# 001_full_version.net
KiCad netlist of a schematic drawn in EAGLE
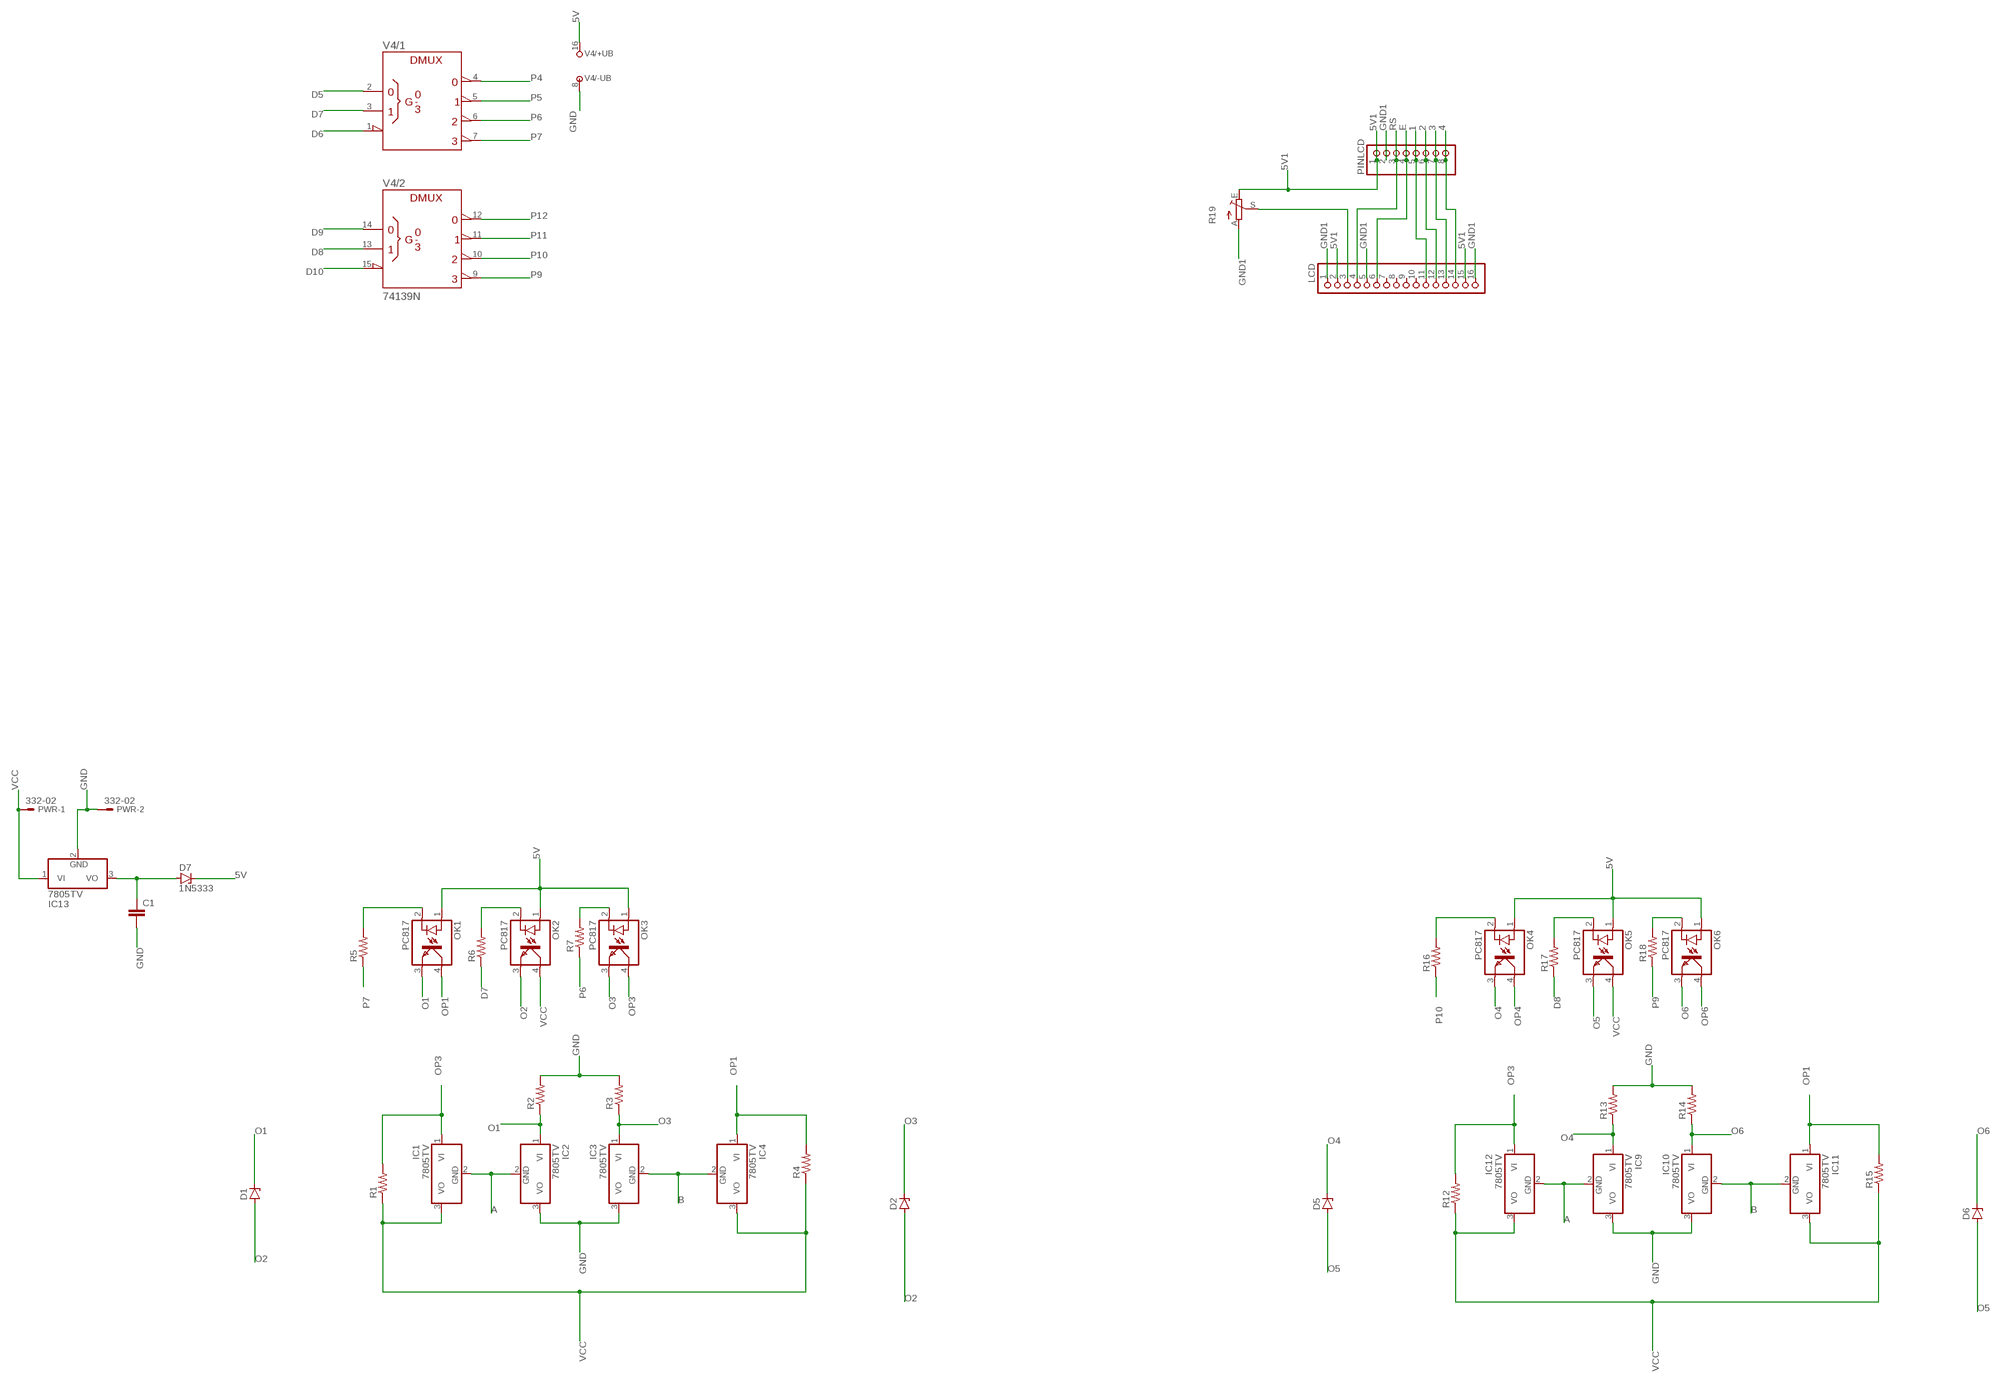
[diagram p0: schematic, sheet 1]

(export (version "E")
  (design (tool "Eeschema 10.0.6"))
  (components
    (comp (ref "C1")
      (value "C2,5-3")
      (footprint "eagle-import:C2.5-3")
      (libsource (lib "eagle-import") (part "C2,5-3"))
    )
    (comp (ref "D1")
      (value "ZENER-DIODEDO41Z10")
      (footprint "eagle-import:DO41Z10")
      (libsource (lib "eagle-import") (part "ZENER-DIODEDO41Z10"))
    )
    (comp (ref "D2")
      (value "ZENER-DIODEDO41Z10")
      (footprint "eagle-import:DO41Z10")
      (libsource (lib "eagle-import") (part "ZENER-DIODEDO41Z10"))
    )
    (comp (ref "D5")
      (value "ZENER-DIODEDO41Z10")
      (footprint "eagle-import:DO41Z10")
      (libsource (lib "eagle-import") (part "ZENER-DIODEDO41Z10"))
    )
    (comp (ref "D6")
      (value "ZENER-DIODEDO41Z10")
      (footprint "eagle-import:DO41Z10")
      (libsource (lib "eagle-import") (part "ZENER-DIODEDO41Z10"))
    )
    (comp (ref "D7")
      (value "1N5333")
      (footprint "eagle-import:C1702-15")
      (libsource (lib "eagle-import") (part "1N5333"))
    )
    (comp (ref "IC1")
      (value "7805TV")
      (footprint "eagle-import:TO220V")
      (libsource (lib "eagle-import") (part "78TV05"))
    )
    (comp (ref "IC2")
      (value "7805TV")
      (footprint "eagle-import:TO220V")
      (libsource (lib "eagle-import") (part "78TV05"))
    )
    (comp (ref "IC3")
      (value "7805TV")
      (footprint "eagle-import:TO220V")
      (libsource (lib "eagle-import") (part "78TV05"))
    )
    (comp (ref "IC4")
      (value "7805TV")
      (footprint "eagle-import:TO220V")
      (libsource (lib "eagle-import") (part "78TV05"))
    )
    (comp (ref "IC9")
      (value "7805TV")
      (footprint "eagle-import:TO220V")
      (libsource (lib "eagle-import") (part "78TV05"))
    )
    (comp (ref "IC10")
      (value "7805TV")
      (footprint "eagle-import:TO220V")
      (libsource (lib "eagle-import") (part "78TV05"))
    )
    (comp (ref "IC11")
      (value "7805TV")
      (footprint "eagle-import:TO220V")
      (libsource (lib "eagle-import") (part "78TV05"))
    )
    (comp (ref "IC12")
      (value "7805TV")
      (footprint "eagle-import:TO220V")
      (libsource (lib "eagle-import") (part "78TV05"))
    )
    (comp (ref "IC13")
      (value "7805TV")
      (footprint "eagle-import:TO220V")
      (libsource (lib "eagle-import") (part "78TV05"))
    )
    (comp (ref "LCD")
      (value "PINHD-1X16")
      (footprint "eagle-import:1X16")
      (libsource (lib "eagle-import") (part "PINHD-1X16"))
    )
    (comp (ref "OK1")
      (value "PC817")
      (footprint "eagle-import:DIL04")
      (fields (field (name "MPN") "PC817X4J000F"))
      (libsource (lib "eagle-import") (part "PC817"))
    )
    (comp (ref "OK2")
      (value "PC817")
      (footprint "eagle-import:DIL04")
      (fields (field (name "MPN") "PC817X4J000F"))
      (libsource (lib "eagle-import") (part "PC817"))
    )
    (comp (ref "OK3")
      (value "PC817")
      (footprint "eagle-import:DIL04")
      (fields (field (name "MPN") "PC817X4J000F"))
      (libsource (lib "eagle-import") (part "PC817"))
    )
    (comp (ref "OK4")
      (value "PC817")
      (footprint "eagle-import:DIL04")
      (fields (field (name "MPN") "PC817X4J000F"))
      (libsource (lib "eagle-import") (part "PC817"))
    )
    (comp (ref "OK5")
      (value "PC817")
      (footprint "eagle-import:DIL04")
      (fields (field (name "MPN") "PC817X4J000F"))
      (libsource (lib "eagle-import") (part "PC817"))
    )
    (comp (ref "OK6")
      (value "PC817")
      (footprint "eagle-import:DIL04")
      (fields (field (name "MPN") "PC817X4J000F"))
      (libsource (lib "eagle-import") (part "PC817"))
    )
    (comp (ref "PINLCD")
      (value "PINHD-1X8")
      (footprint "eagle-import:1X08")
      (libsource (lib "eagle-import") (part "PINHD-1X8"))
    )
    (comp (ref "PWR")
      (value "332-02")
      (footprint "eagle-import:332-02")
      (libsource (lib "eagle-import") (part "332-02"))
    )
    (comp (ref "R1")
      (value "R-US_M0805")
      (footprint "eagle-import:M0805")
      (libsource (lib "eagle-import") (part "R-US_M0805"))
    )
    (comp (ref "R2")
      (value "R-US_M0805")
      (footprint "eagle-import:M0805")
      (libsource (lib "eagle-import") (part "R-US_M0805"))
    )
    (comp (ref "R3")
      (value "R-US_M0805")
      (footprint "eagle-import:M0805")
      (libsource (lib "eagle-import") (part "R-US_M0805"))
    )
    (comp (ref "R4")
      (value "R-US_M0805")
      (footprint "eagle-import:M0805")
      (libsource (lib "eagle-import") (part "R-US_M0805"))
    )
    (comp (ref "R5")
      (value "R-US_M0805")
      (footprint "eagle-import:M0805")
      (libsource (lib "eagle-import") (part "R-US_M0805"))
    )
    (comp (ref "R6")
      (value "R-US_M0805")
      (footprint "eagle-import:M0805")
      (libsource (lib "eagle-import") (part "R-US_M0805"))
    )
    (comp (ref "R7")
      (value "R-US_M0805")
      (footprint "eagle-import:M0805")
      (libsource (lib "eagle-import") (part "R-US_M0805"))
    )
    (comp (ref "R12")
      (value "R-US_M0805")
      (footprint "eagle-import:M0805")
      (libsource (lib "eagle-import") (part "R-US_M0805"))
    )
    (comp (ref "R13")
      (value "R-US_M0805")
      (footprint "eagle-import:M0805")
      (libsource (lib "eagle-import") (part "R-US_M0805"))
    )
    (comp (ref "R14")
      (value "R-US_M0805")
      (footprint "eagle-import:M0805")
      (libsource (lib "eagle-import") (part "R-US_M0805"))
    )
    (comp (ref "R15")
      (value "R-US_M0805")
      (footprint "eagle-import:M0805")
      (libsource (lib "eagle-import") (part "R-US_M0805"))
    )
    (comp (ref "R16")
      (value "R-US_M0805")
      (footprint "eagle-import:M0805")
      (libsource (lib "eagle-import") (part "R-US_M0805"))
    )
    (comp (ref "R17")
      (value "R-US_M0805")
      (footprint "eagle-import:M0805")
      (libsource (lib "eagle-import") (part "R-US_M0805"))
    )
    (comp (ref "R18")
      (value "R-US_M0805")
      (footprint "eagle-import:M0805")
      (libsource (lib "eagle-import") (part "R-US_M0805"))
    )
    (comp (ref "R19")
      (value "TRIM_EU-B25U")
      (footprint "eagle-import:B25U")
      (libsource (lib "eagle-import") (part "TRIM_EU-B25U"))
    )
    (comp (ref "V4")
      (value "74139N")
      (footprint "eagle-import:DIL16")
      (libsource (lib "eagle-import") (part "74139N"))
    )
  )
  (nets
    (net (code "1") (name "/1") (class "Default")
      (node (ref "LCD") (pin "11") (pinfunction "11_11") (pintype "passive"))
      (node (ref "PINLCD") (pin "5") (pinfunction "5_5") (pintype "passive"))
    )
    (net (code "2") (name "/2") (class "Default")
      (node (ref "LCD") (pin "12") (pinfunction "12_12") (pintype "passive"))
      (node (ref "PINLCD") (pin "6") (pinfunction "6_6") (pintype "passive"))
    )
    (net (code "3") (name "/3") (class "Default")
      (node (ref "LCD") (pin "13") (pinfunction "13_13") (pintype "passive"))
      (node (ref "PINLCD") (pin "7") (pinfunction "7_7") (pintype "passive"))
    )
    (net (code "4") (name "/4") (class "Default")
      (node (ref "LCD") (pin "14") (pinfunction "14_14") (pintype "passive"))
      (node (ref "PINLCD") (pin "8") (pinfunction "8_8") (pintype "passive"))
    )
    (net (code "5") (name "/5V") (class "Default")
      (node (ref "D7") (pin "C") (pinfunction "C_C") (pintype "passive"))
      (node (ref "OK1") (pin "1") (pinfunction "A_1") (pintype "passive"))
      (node (ref "OK2") (pin "1") (pinfunction "A_1") (pintype "passive"))
      (node (ref "OK3") (pin "1") (pinfunction "A_1") (pintype "passive"))
      (node (ref "OK4") (pin "1") (pinfunction "A_1") (pintype "passive"))
      (node (ref "OK5") (pin "1") (pinfunction "A_1") (pintype "passive"))
      (node (ref "OK6") (pin "1") (pinfunction "A_1") (pintype "passive"))
      (node (ref "V4") (pin "16") (pinfunction "+UB_16") (pintype "power_in"))
    )
    (net (code "6") (name "/5V1") (class "Default")
      (node (ref "LCD") (pin "15") (pinfunction "15_15") (pintype "passive"))
      (node (ref "LCD") (pin "2") (pinfunction "2_2") (pintype "passive"))
      (node (ref "PINLCD") (pin "1") (pinfunction "1_1") (pintype "passive"))
      (node (ref "R19") (pin "E") (pinfunction "E_E") (pintype "passive"))
    )
    (net (code "7") (name "/A") (class "Default")
      (node (ref "IC1") (pin "2") (pinfunction "GND_2") (pintype "passive"))
      (node (ref "IC12") (pin "2") (pinfunction "GND_2") (pintype "passive"))
      (node (ref "IC2") (pin "2") (pinfunction "GND_2") (pintype "passive"))
      (node (ref "IC9") (pin "2") (pinfunction "GND_2") (pintype "passive"))
    )
    (net (code "8") (name "/B") (class "Default")
      (node (ref "IC10") (pin "2") (pinfunction "GND_2") (pintype "passive"))
      (node (ref "IC11") (pin "2") (pinfunction "GND_2") (pintype "passive"))
      (node (ref "IC3") (pin "2") (pinfunction "GND_2") (pintype "passive"))
      (node (ref "IC4") (pin "2") (pinfunction "GND_2") (pintype "passive"))
    )
    (net (code "9") (name "/D5") (class "Default")
      (node (ref "V4") (pin "2") (pinfunction "A_2") (pintype "input"))
    )
    (net (code "10") (name "/D6") (class "Default")
      (node (ref "V4") (pin "1") (pinfunction "~{G}_1") (pintype "input"))
    )
    (net (code "11") (name "/D7") (class "Default")
      (node (ref "R6") (pin "1") (pinfunction "1_1") (pintype "passive"))
      (node (ref "V4") (pin "3") (pinfunction "B_3") (pintype "input"))
    )
    (net (code "12") (name "/D8") (class "Default")
      (node (ref "R17") (pin "1") (pinfunction "1_1") (pintype "passive"))
      (node (ref "V4") (pin "13") (pinfunction "B_13") (pintype "input"))
    )
    (net (code "13") (name "/D9") (class "Default")
      (node (ref "V4") (pin "14") (pinfunction "A_14") (pintype "input"))
    )
    (net (code "14") (name "/D10") (class "Default")
      (node (ref "V4") (pin "15") (pinfunction "~{G}_15") (pintype "input"))
    )
    (net (code "15") (name "/E") (class "Default")
      (node (ref "LCD") (pin "6") (pinfunction "6_6") (pintype "passive"))
      (node (ref "PINLCD") (pin "4") (pinfunction "4_4") (pintype "passive"))
    )
    (net (code "16") (name "/GND") (class "Default")
      (node (ref "C1") (pin "2") (pinfunction "2_2") (pintype "passive"))
      (node (ref "IC10") (pin "3") (pinfunction "VO_3") (pintype "passive"))
      (node (ref "IC13") (pin "2") (pinfunction "GND_2") (pintype "passive"))
      (node (ref "IC2") (pin "3") (pinfunction "VO_3") (pintype "passive"))
      (node (ref "IC3") (pin "3") (pinfunction "VO_3") (pintype "passive"))
      (node (ref "IC9") (pin "3") (pinfunction "VO_3") (pintype "passive"))
      (node (ref "PWR") (pin "2") (pinfunction "S_2") (pintype "passive"))
      (node (ref "R13") (pin "2") (pinfunction "2_2") (pintype "passive"))
      (node (ref "R14") (pin "2") (pinfunction "2_2") (pintype "passive"))
      (node (ref "R2") (pin "2") (pinfunction "2_2") (pintype "passive"))
      (node (ref "R3") (pin "2") (pinfunction "2_2") (pintype "passive"))
      (node (ref "V4") (pin "8") (pinfunction "-UB_8") (pintype "power_in"))
    )
    (net (code "17") (name "/GND1") (class "Default")
      (node (ref "LCD") (pin "1") (pinfunction "1_1") (pintype "passive"))
      (node (ref "LCD") (pin "16") (pinfunction "16_16") (pintype "passive"))
      (node (ref "LCD") (pin "5") (pinfunction "5_5") (pintype "passive"))
      (node (ref "PINLCD") (pin "2") (pinfunction "2_2") (pintype "passive"))
      (node (ref "R19") (pin "A") (pinfunction "A_A") (pintype "passive"))
    )
    (net (code "18") (name "/O1") (class "Default")
      (node (ref "D1") (pin "C") (pinfunction "C_C") (pintype "passive"))
      (node (ref "IC2") (pin "1") (pinfunction "VI_1") (pintype "input"))
      (node (ref "OK1") (pin "3") (pinfunction "EMIT_3") (pintype "passive"))
      (node (ref "R2") (pin "1") (pinfunction "1_1") (pintype "passive"))
    )
    (net (code "19") (name "/O2") (class "Default")
      (node (ref "D1") (pin "A") (pinfunction "A_A") (pintype "passive"))
      (node (ref "D2") (pin "A") (pinfunction "A_A") (pintype "passive"))
      (node (ref "OK2") (pin "3") (pinfunction "EMIT_3") (pintype "passive"))
    )
    (net (code "20") (name "/O3") (class "Default")
      (node (ref "D2") (pin "C") (pinfunction "C_C") (pintype "passive"))
      (node (ref "IC3") (pin "1") (pinfunction "VI_1") (pintype "input"))
      (node (ref "OK3") (pin "3") (pinfunction "EMIT_3") (pintype "passive"))
      (node (ref "R3") (pin "1") (pinfunction "1_1") (pintype "passive"))
    )
    (net (code "21") (name "/O4") (class "Default")
      (node (ref "D5") (pin "C") (pinfunction "C_C") (pintype "passive"))
      (node (ref "IC9") (pin "1") (pinfunction "VI_1") (pintype "input"))
      (node (ref "OK4") (pin "3") (pinfunction "EMIT_3") (pintype "passive"))
      (node (ref "R13") (pin "1") (pinfunction "1_1") (pintype "passive"))
    )
    (net (code "22") (name "/O5") (class "Default")
      (node (ref "D5") (pin "A") (pinfunction "A_A") (pintype "passive"))
      (node (ref "D6") (pin "A") (pinfunction "A_A") (pintype "passive"))
      (node (ref "OK5") (pin "3") (pinfunction "EMIT_3") (pintype "passive"))
    )
    (net (code "23") (name "/O6") (class "Default")
      (node (ref "D6") (pin "C") (pinfunction "C_C") (pintype "passive"))
      (node (ref "IC10") (pin "1") (pinfunction "VI_1") (pintype "input"))
      (node (ref "OK6") (pin "3") (pinfunction "EMIT_3") (pintype "passive"))
      (node (ref "R14") (pin "1") (pinfunction "1_1") (pintype "passive"))
    )
    (net (code "24") (name "/OP1") (class "Default")
      (node (ref "IC11") (pin "1") (pinfunction "VI_1") (pintype "input"))
      (node (ref "IC4") (pin "1") (pinfunction "VI_1") (pintype "input"))
      (node (ref "OK1") (pin "4") (pinfunction "COL_4") (pintype "passive"))
      (node (ref "R15") (pin "2") (pinfunction "2_2") (pintype "passive"))
      (node (ref "R4") (pin "2") (pinfunction "2_2") (pintype "passive"))
    )
    (net (code "25") (name "/OP3") (class "Default")
      (node (ref "IC1") (pin "1") (pinfunction "VI_1") (pintype "input"))
      (node (ref "IC12") (pin "1") (pinfunction "VI_1") (pintype "input"))
      (node (ref "OK3") (pin "4") (pinfunction "COL_4") (pintype "passive"))
      (node (ref "R1") (pin "2") (pinfunction "2_2") (pintype "passive"))
      (node (ref "R12") (pin "2") (pinfunction "2_2") (pintype "passive"))
    )
    (net (code "26") (name "/OP4") (class "Default")
      (node (ref "OK4") (pin "4") (pinfunction "COL_4") (pintype "passive"))
    )
    (net (code "27") (name "/OP6") (class "Default")
      (node (ref "OK6") (pin "4") (pinfunction "COL_4") (pintype "passive"))
    )
    (net (code "28") (name "/P4") (class "Default")
      (node (ref "V4") (pin "4") (pinfunction "Y0_4") (pintype "output"))
    )
    (net (code "29") (name "/P5") (class "Default")
      (node (ref "V4") (pin "5") (pinfunction "Y1_5") (pintype "output"))
    )
    (net (code "30") (name "/P6") (class "Default")
      (node (ref "R7") (pin "1") (pinfunction "1_1") (pintype "passive"))
      (node (ref "V4") (pin "6") (pinfunction "Y2_6") (pintype "output"))
    )
    (net (code "31") (name "/P7") (class "Default")
      (node (ref "R5") (pin "1") (pinfunction "1_1") (pintype "passive"))
      (node (ref "V4") (pin "7") (pinfunction "Y3_7") (pintype "output"))
    )
    (net (code "32") (name "/P9") (class "Default")
      (node (ref "R18") (pin "1") (pinfunction "1_1") (pintype "passive"))
      (node (ref "V4") (pin "9") (pinfunction "Y3_9") (pintype "output"))
    )
    (net (code "33") (name "/P10") (class "Default")
      (node (ref "R16") (pin "1") (pinfunction "1_1") (pintype "passive"))
      (node (ref "V4") (pin "10") (pinfunction "Y2_10") (pintype "output"))
    )
    (net (code "34") (name "/P11") (class "Default")
      (node (ref "V4") (pin "11") (pinfunction "Y1_11") (pintype "output"))
    )
    (net (code "35") (name "/P12") (class "Default")
      (node (ref "V4") (pin "12") (pinfunction "Y0_12") (pintype "output"))
    )
    (net (code "36") (name "/RS") (class "Default")
      (node (ref "LCD") (pin "4") (pinfunction "4_4") (pintype "passive"))
      (node (ref "PINLCD") (pin "3") (pinfunction "3_3") (pintype "passive"))
    )
    (net (code "37") (name "/VCC") (class "Default")
      (node (ref "IC1") (pin "3") (pinfunction "VO_3") (pintype "passive"))
      (node (ref "IC11") (pin "3") (pinfunction "VO_3") (pintype "passive"))
      (node (ref "IC12") (pin "3") (pinfunction "VO_3") (pintype "passive"))
      (node (ref "IC13") (pin "1") (pinfunction "VI_1") (pintype "input"))
      (node (ref "IC4") (pin "3") (pinfunction "VO_3") (pintype "passive"))
      (node (ref "OK2") (pin "4") (pinfunction "COL_4") (pintype "passive"))
      (node (ref "OK5") (pin "4") (pinfunction "COL_4") (pintype "passive"))
      (node (ref "PWR") (pin "1") (pinfunction "S_1") (pintype "passive"))
      (node (ref "R1") (pin "1") (pinfunction "1_1") (pintype "passive"))
      (node (ref "R12") (pin "1") (pinfunction "1_1") (pintype "passive"))
      (node (ref "R15") (pin "1") (pinfunction "1_1") (pintype "passive"))
      (node (ref "R4") (pin "1") (pinfunction "1_1") (pintype "passive"))
    )
    (net (code "38") (name "Net-(IC13-VO)") (class "Default")
      (node (ref "C1") (pin "1") (pinfunction "1_1") (pintype "passive"))
      (node (ref "D7") (pin "A") (pinfunction "A_A") (pintype "passive"))
      (node (ref "IC13") (pin "3") (pinfunction "VO_3") (pintype "passive"))
    )
    (net (code "39") (name "Net-(LCD-Pad3)") (class "Default")
      (node (ref "LCD") (pin "3") (pinfunction "3_3") (pintype "passive"))
      (node (ref "R19") (pin "S") (pinfunction "S_S") (pintype "passive"))
    )
    (net (code "40") (name "Net-(OK1-C)") (class "Default")
      (node (ref "OK1") (pin "2") (pinfunction "C_2") (pintype "passive"))
      (node (ref "R5") (pin "2") (pinfunction "2_2") (pintype "passive"))
    )
    (net (code "41") (name "Net-(OK2-C)") (class "Default")
      (node (ref "OK2") (pin "2") (pinfunction "C_2") (pintype "passive"))
      (node (ref "R6") (pin "2") (pinfunction "2_2") (pintype "passive"))
    )
    (net (code "42") (name "Net-(OK3-C)") (class "Default")
      (node (ref "OK3") (pin "2") (pinfunction "C_2") (pintype "passive"))
      (node (ref "R7") (pin "2") (pinfunction "2_2") (pintype "passive"))
    )
    (net (code "43") (name "Net-(OK4-C)") (class "Default")
      (node (ref "OK4") (pin "2") (pinfunction "C_2") (pintype "passive"))
      (node (ref "R16") (pin "2") (pinfunction "2_2") (pintype "passive"))
    )
    (net (code "44") (name "Net-(OK5-C)") (class "Default")
      (node (ref "OK5") (pin "2") (pinfunction "C_2") (pintype "passive"))
      (node (ref "R17") (pin "2") (pinfunction "2_2") (pintype "passive"))
    )
    (net (code "45") (name "Net-(OK6-C)") (class "Default")
      (node (ref "OK6") (pin "2") (pinfunction "C_2") (pintype "passive"))
      (node (ref "R18") (pin "2") (pinfunction "2_2") (pintype "passive"))
    )
    (net (code "46") (name "unconnected-(LCD-Pad7)") (class "Default")
      (node (ref "LCD") (pin "7") (pinfunction "7_7") (pintype "passive"))
    )
    (net (code "47") (name "unconnected-(LCD-Pad8)") (class "Default")
      (node (ref "LCD") (pin "8") (pinfunction "8_8") (pintype "passive"))
    )
    (net (code "48") (name "unconnected-(LCD-Pad9)") (class "Default")
      (node (ref "LCD") (pin "9") (pinfunction "9_9") (pintype "passive"))
    )
    (net (code "49") (name "unconnected-(LCD-Pad10)") (class "Default")
      (node (ref "LCD") (pin "10") (pinfunction "10_10") (pintype "passive"))
    )
  )
)
